# water_ver4_00.net
KiCad netlist of a schematic drawn in EAGLE
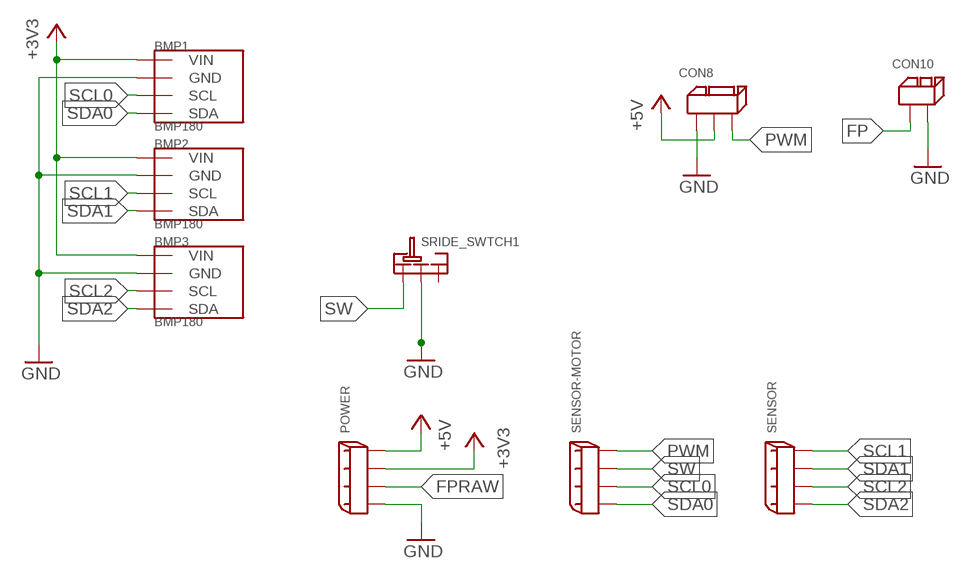
[diagram p0: schematic, sheet 1]

(export (version "E")
  (design (tool "Eeschema 10.0.6"))
  (components
    (comp (ref "BMP1")
      (value "BMP180")
      (footprint "eagle-import:GY-68")
      (libsource (lib "eagle-import") (part "BMP180"))
    )
    (comp (ref "BMP2")
      (value "BMP180")
      (footprint "eagle-import:GY-68")
      (libsource (lib "eagle-import") (part "BMP180"))
    )
    (comp (ref "BMP3")
      (value "BMP180")
      (footprint "eagle-import:GY-68")
      (libsource (lib "eagle-import") (part "BMP180"))
    )
    (comp (ref "CON8")
      (value "3PIN")
      (footprint "eagle-import:3PIN")
      (libsource (lib "eagle-import") (part "3PIN"))
    )
    (comp (ref "CON10")
      (value "2PIN")
      (footprint "eagle-import:2PIN")
      (libsource (lib "eagle-import") (part "2PIN"))
    )
    (comp (ref "POWER")
      (value "2.5_MINI-SPOX_4PIN")
      (footprint "eagle-import:2.5_MINI-SPOX_4PIN")
      (libsource (lib "eagle-import") (part "2.5_MINI-SPOX_4PIN"))
    )
    (comp (ref "SENSOR")
      (value "2.5_MINI-SPOX_4PIN")
      (footprint "eagle-import:2.5_MINI-SPOX_4PIN")
      (libsource (lib "eagle-import") (part "2.5_MINI-SPOX_4PIN"))
    )
    (comp (ref "SENSOR-MOTOR")
      (value "2.5_MINI-SPOX_4PIN")
      (footprint "eagle-import:2.5_MINI-SPOX_4PIN")
      (libsource (lib "eagle-import") (part "2.5_MINI-SPOX_4PIN"))
    )
    (comp (ref "SRIDE_SWTCH1")
      (value "SRIDE_SWITCH")
      (footprint "eagle-import:SRIDE_SWITCH")
      (libsource (lib "eagle-import") (part "SRIDE_SWITCH"))
    )
  )
  (nets
    (net (code "1") (name "+3V3") (class "Default")
      (node (ref "BMP1") (pin "P1") (pinfunction "VIN_P1") (pintype "bidirectional"))
      (node (ref "BMP2") (pin "P1") (pinfunction "VIN_P1") (pintype "bidirectional"))
      (node (ref "BMP3") (pin "P1") (pinfunction "VIN_P1") (pintype "bidirectional"))
      (node (ref "POWER") (pin "P$3") (pinfunction "3_P$3") (pintype "bidirectional"))
    )
    (net (code "2") (name "+5V") (class "Default")
      (node (ref "CON8") (pin "P$2") (pinfunction "P$2_P$2") (pintype "bidirectional"))
      (node (ref "POWER") (pin "P$4") (pinfunction "4_P$4") (pintype "bidirectional"))
    )
    (net (code "3") (name "FP") (class "Default")
      (node (ref "CON10") (pin "P$1") (pinfunction "P$1_P$1") (pintype "bidirectional"))
    )
    (net (code "4") (name "FPRAW") (class "Default")
      (node (ref "POWER") (pin "P$2") (pinfunction "2_P$2") (pintype "bidirectional"))
    )
    (net (code "5") (name "GND") (class "Default")
      (node (ref "BMP1") (pin "P2") (pinfunction "GND_P2") (pintype "bidirectional"))
      (node (ref "BMP2") (pin "P2") (pinfunction "GND_P2") (pintype "bidirectional"))
      (node (ref "BMP3") (pin "P2") (pinfunction "GND_P2") (pintype "bidirectional"))
      (node (ref "CON10") (pin "P$2") (pinfunction "P$2_P$2") (pintype "bidirectional"))
      (node (ref "CON8") (pin "P$1") (pinfunction "P$1_P$1") (pintype "bidirectional"))
      (node (ref "POWER") (pin "P$1") (pinfunction "1_P$1") (pintype "bidirectional"))
      (node (ref "SRIDE_SWTCH1") (pin "LR") (pinfunction "LR_LR") (pintype "bidirectional"))
    )
    (net (code "6") (name "PWM") (class "Default")
      (node (ref "CON8") (pin "P$3") (pinfunction "P$3_P$3") (pintype "bidirectional"))
      (node (ref "SENSOR-MOTOR") (pin "P$4") (pinfunction "4_P$4") (pintype "bidirectional"))
    )
    (net (code "7") (name "SCL0") (class "Default")
      (node (ref "BMP1") (pin "P3") (pinfunction "SCL_P3") (pintype "bidirectional"))
      (node (ref "SENSOR-MOTOR") (pin "P$2") (pinfunction "2_P$2") (pintype "bidirectional"))
    )
    (net (code "8") (name "SCL1") (class "Default")
      (node (ref "BMP2") (pin "P3") (pinfunction "SCL_P3") (pintype "bidirectional"))
      (node (ref "SENSOR") (pin "P$4") (pinfunction "4_P$4") (pintype "bidirectional"))
    )
    (net (code "9") (name "SCL2") (class "Default")
      (node (ref "BMP3") (pin "P3") (pinfunction "SCL_P3") (pintype "bidirectional"))
      (node (ref "SENSOR") (pin "P$2") (pinfunction "2_P$2") (pintype "bidirectional"))
    )
    (net (code "10") (name "SDA0") (class "Default")
      (node (ref "BMP1") (pin "P4") (pinfunction "SDA_P4") (pintype "bidirectional"))
      (node (ref "SENSOR-MOTOR") (pin "P$1") (pinfunction "1_P$1") (pintype "bidirectional"))
    )
    (net (code "11") (name "SDA1") (class "Default")
      (node (ref "BMP2") (pin "P4") (pinfunction "SDA_P4") (pintype "bidirectional"))
      (node (ref "SENSOR") (pin "P$3") (pinfunction "3_P$3") (pintype "bidirectional"))
    )
    (net (code "12") (name "SDA2") (class "Default")
      (node (ref "BMP3") (pin "P4") (pinfunction "SDA_P4") (pintype "bidirectional"))
      (node (ref "SENSOR") (pin "P$1") (pinfunction "1_P$1") (pintype "bidirectional"))
    )
    (net (code "13") (name "SW") (class "Default")
      (node (ref "SENSOR-MOTOR") (pin "P$3") (pinfunction "3_P$3") (pintype "bidirectional"))
      (node (ref "SRIDE_SWTCH1") (pin "L") (pinfunction "L_L") (pintype "bidirectional"))
    )
    (net (code "14") (name "unconnected-(SRIDE_SWTCH1-PadR)") (class "Default")
      (node (ref "SRIDE_SWTCH1") (pin "R") (pinfunction "R_R") (pintype "bidirectional"))
    )
  )
)
